# Fri3D_2026_Audio.net
KiCad netlist of a schematic drawn in Altium Designer
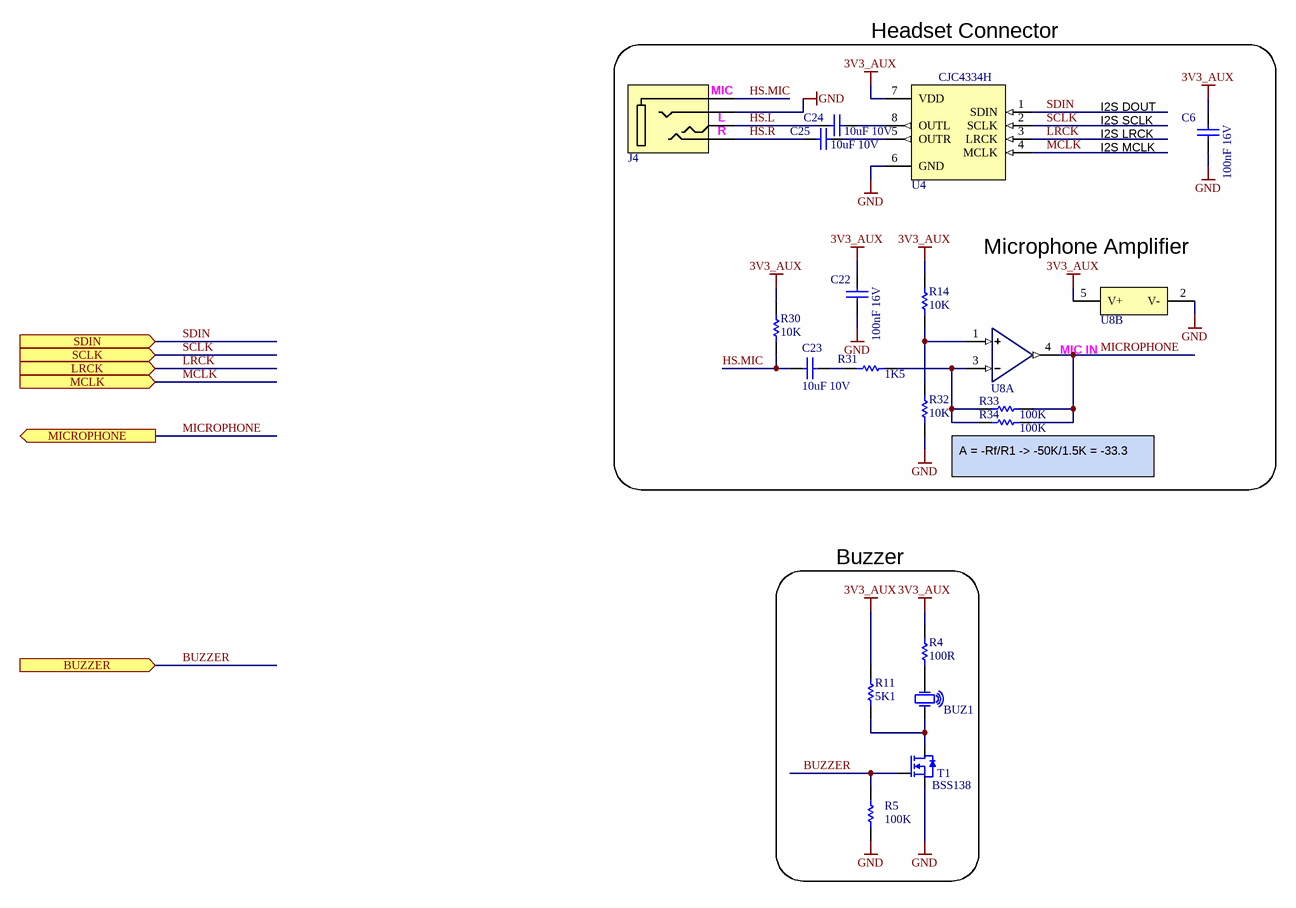
[diagram p0: Fri3D_2026_Audio.SchDoc]

(export (version "E")
  (design (tool "Eeschema 10.0.6"))
  (components
    (comp (ref "BUZ1")
      (value "12x12x3mm Piezo Buzzer Transducer 81dB")
      (footprint "CUI_CMT-1203-SMT")
      (description "Crystal Oscillator")
      (libsource (lib "Phyx_Components") (part "Buzzer"))
    )
    (comp (ref "C6")
      (value "100nF 16V")
      (footprint "C0603_N")
      (description "Capacitor Ceramic")
      (libsource (lib "Phyx_Components") (part "CAP_CERAMIC"))
    )
    (comp (ref "C22")
      (value "100nF 16V")
      (footprint "C0603_N")
      (description "Capacitor Ceramic")
      (libsource (lib "Phyx_Components") (part "CAP_CERAMIC"))
    )
    (comp (ref "C23")
      (value "10uF 10V")
      (footprint "C0805_N")
      (description "Capacitor Ceramic")
      (libsource (lib "Phyx_Components") (part "CAP_CERAMIC"))
    )
    (comp (ref "C24")
      (value "10uF 10V")
      (footprint "C0805_N")
      (description "Capacitor Ceramic")
      (libsource (lib "Phyx_Components") (part "CAP_CERAMIC"))
    )
    (comp (ref "C25")
      (value "10uF 10V")
      (footprint "C0805_N")
      (description "Capacitor Ceramic")
      (libsource (lib "Phyx_Components") (part "CAP_CERAMIC"))
    )
    (comp (ref "J4")
      (value "3.5mm jack, black, 4 contacts 15mm")
      (footprint "CAX_PJ-327F-5PS")
      (libsource (lib "Phyx_Components") (part "AUDIO_SRRT-1234"))
    )
    (comp (ref "R4")
      (value "100R")
      (footprint "R0603_N")
      (libsource (lib "Phyx_Components") (part "RESISTOR"))
    )
    (comp (ref "R5")
      (value "100K")
      (footprint "R0603_N")
      (libsource (lib "Phyx_Components") (part "RESISTOR"))
    )
    (comp (ref "R11")
      (value "5K1")
      (footprint "R0603_N")
      (description "RES # 5K1 0603")
      (fields (field (name "Comment") "RESISTOR"))
      (libsource (lib "Phyx_Components") (part "RESISTOR"))
    )
    (comp (ref "R14")
      (value "10K")
      (footprint "R0603_N")
      (libsource (lib "Phyx_Components") (part "RESISTOR"))
    )
    (comp (ref "R30")
      (value "10K")
      (footprint "R0603_N")
      (libsource (lib "Phyx_Components") (part "RESISTOR"))
    )
    (comp (ref "R31")
      (value "1K5")
      (footprint "R0603_N")
      (libsource (lib "Phyx_Components") (part "RESISTOR"))
    )
    (comp (ref "R32")
      (value "10K")
      (footprint "R0603_N")
      (libsource (lib "Phyx_Components") (part "RESISTOR"))
    )
    (comp (ref "R33")
      (value "100K")
      (footprint "R0603_N")
      (libsource (lib "Phyx_Components") (part "RESISTOR"))
    )
    (comp (ref "R34")
      (value "100K")
      (footprint "R0603_N")
      (libsource (lib "Phyx_Components") (part "RESISTOR"))
    )
    (comp (ref "T1")
      (value "BSS138")
      (footprint "SOT23-3")
      (fields (field (name "Comment") "0.2A N-Ch MOSFET Vgs 3.2"))
      (libsource (lib "Phyx_Components") (part "N_MOSFET_GSD"))
    )
    (comp (ref "U4")
      (value "CJC4334H")
      (footprint "SOIC_N_8")
      (description "I2S Stereo DAC with 24-Bit, 192 kHz Stereo D/A Converter")
      (fields (field (name "Comment") "I²S 24bit 192kHz 3V~3.6V DAC"))
      (libsource (lib "Phyx_Components") (part "CSC_CJC4334H"))
    )
    (comp (ref "U8")
      (value "Single, 30-V, 1-MHz operational amplifier")
      (footprint "TI_DBV_R-PDSO-G5")
      (description "=Description")
      (libsource (lib "Phyx_Components") (part "TI_LM321"))
    )
  )
  (nets
    (net (code "1") (name "/BUZZER") (class "Default")
      (node (ref "R5") (pin "1") (pinfunction "1_1") (pintype "passive"))
      (node (ref "T1") (pin "1") (pinfunction "G_1") (pintype "passive"))
    )
    (net (code "2") (name "/HS.L") (class "Default")
      (node (ref "C24") (pin "1") (pinfunction "1_1") (pintype "passive"))
      (node (ref "J4") (pin "4") (pinfunction "Tip_4") (pintype "passive"))
    )
    (net (code "3") (name "/HS.MIC") (class "Default")
      (node (ref "C23") (pin "1") (pinfunction "1_1") (pintype "passive"))
      (node (ref "J4") (pin "1") (pinfunction "Sleeve_1") (pintype "passive"))
      (node (ref "R30") (pin "2") (pinfunction "2_2") (pintype "passive"))
    )
    (net (code "4") (name "/HS.R") (class "Default")
      (node (ref "C25") (pin "1") (pinfunction "1_1") (pintype "passive"))
      (node (ref "J4") (pin "3") (pinfunction "Ring_3") (pintype "passive"))
    )
    (net (code "5") (name "/LRCK") (class "Default")
      (node (ref "U4") (pin "3") (pinfunction "LRCK_3") (pintype "input"))
    )
    (net (code "6") (name "/MCLK") (class "Default")
      (node (ref "U4") (pin "4") (pinfunction "MCLK_4") (pintype "input"))
    )
    (net (code "7") (name "/MICROPHONE") (class "Default")
      (node (ref "R33") (pin "1") (pinfunction "1_1") (pintype "passive"))
      (node (ref "R34") (pin "1") (pinfunction "1_1") (pintype "passive"))
      (node (ref "U8") (pin "4") (pinfunction "OUT_4") (pintype "output"))
    )
    (net (code "8") (name "/SCLK") (class "Default")
      (node (ref "U4") (pin "2") (pinfunction "SCLK_2") (pintype "input"))
    )
    (net (code "9") (name "/SDIN") (class "Default")
      (node (ref "U4") (pin "1") (pinfunction "SDIN_1") (pintype "input"))
    )
    (net (code "10") (name "3V3_AUX") (class "Default")
      (node (ref "C22") (pin "1") (pinfunction "1_1") (pintype "passive"))
      (node (ref "C6") (pin "1") (pinfunction "1_1") (pintype "passive"))
      (node (ref "R11") (pin "2") (pinfunction "2_2") (pintype "passive"))
      (node (ref "R14") (pin "1") (pinfunction "1_1") (pintype "passive"))
      (node (ref "R30") (pin "1") (pinfunction "1_1") (pintype "passive"))
      (node (ref "R4") (pin "2") (pinfunction "2_2") (pintype "passive"))
      (node (ref "U4") (pin "7") (pinfunction "VDD_7") (pintype "power_in"))
      (node (ref "U8") (pin "5") (pinfunction "V+_5") (pintype "power_in"))
    )
    (net (code "11") (name "GND") (class "Default")
      (node (ref "C22") (pin "2") (pinfunction "2_2") (pintype "passive"))
      (node (ref "C6") (pin "2") (pinfunction "2_2") (pintype "passive"))
      (node (ref "J4") (pin "2") (pinfunction "Ring_2") (pintype "passive"))
      (node (ref "R32") (pin "2") (pinfunction "2_2") (pintype "passive"))
      (node (ref "R5") (pin "2") (pinfunction "2_2") (pintype "passive"))
      (node (ref "T1") (pin "2") (pinfunction "S_2") (pintype "passive"))
      (node (ref "U4") (pin "6") (pinfunction "GND_6") (pintype "power_in"))
      (node (ref "U8") (pin "2") (pinfunction "V-_2") (pintype "power_in"))
    )
    (net (code "12") (name "Net-(BUZ1-OSC1)") (class "Default")
      (node (ref "BUZ1") (pin "1") (pinfunction "OSC1_1") (pintype "passive"))
      (node (ref "R11") (pin "1") (pinfunction "1_1") (pintype "passive"))
      (node (ref "T1") (pin "3") (pinfunction "D_3") (pintype "passive"))
    )
    (net (code "13") (name "Net-(BUZ1-OSC2)") (class "Default")
      (node (ref "BUZ1") (pin "2") (pinfunction "OSC2_2") (pintype "passive"))
      (node (ref "R4") (pin "1") (pinfunction "1_1") (pintype "passive"))
    )
    (net (code "14") (name "Net-(C23-Pad2)") (class "Default")
      (node (ref "C23") (pin "2") (pinfunction "2_2") (pintype "passive"))
      (node (ref "R31") (pin "2") (pinfunction "2_2") (pintype "passive"))
    )
    (net (code "15") (name "Net-(U4-OUTL)") (class "Default")
      (node (ref "C24") (pin "2") (pinfunction "2_2") (pintype "passive"))
      (node (ref "U4") (pin "8") (pinfunction "OUTL_8") (pintype "output"))
    )
    (net (code "16") (name "Net-(U4-OUTR)") (class "Default")
      (node (ref "C25") (pin "2") (pinfunction "2_2") (pintype "passive"))
      (node (ref "U4") (pin "5") (pinfunction "OUTR_5") (pintype "output"))
    )
    (net (code "17") (name "Net-(U8A-+)") (class "Default")
      (node (ref "R14") (pin "2") (pinfunction "2_2") (pintype "passive"))
      (node (ref "R32") (pin "1") (pinfunction "1_1") (pintype "passive"))
      (node (ref "U8") (pin "1") (pinfunction "+_1") (pintype "input"))
    )
    (net (code "18") (name "Net-(U8A--)") (class "Default")
      (node (ref "R31") (pin "1") (pinfunction "1_1") (pintype "passive"))
      (node (ref "R33") (pin "2") (pinfunction "2_2") (pintype "passive"))
      (node (ref "R34") (pin "2") (pinfunction "2_2") (pintype "passive"))
      (node (ref "U8") (pin "3") (pinfunction "-_3") (pintype "input"))
    )
  )
)
